# 3_PWR.net
KiCad netlist of a schematic drawn in Altium Designer
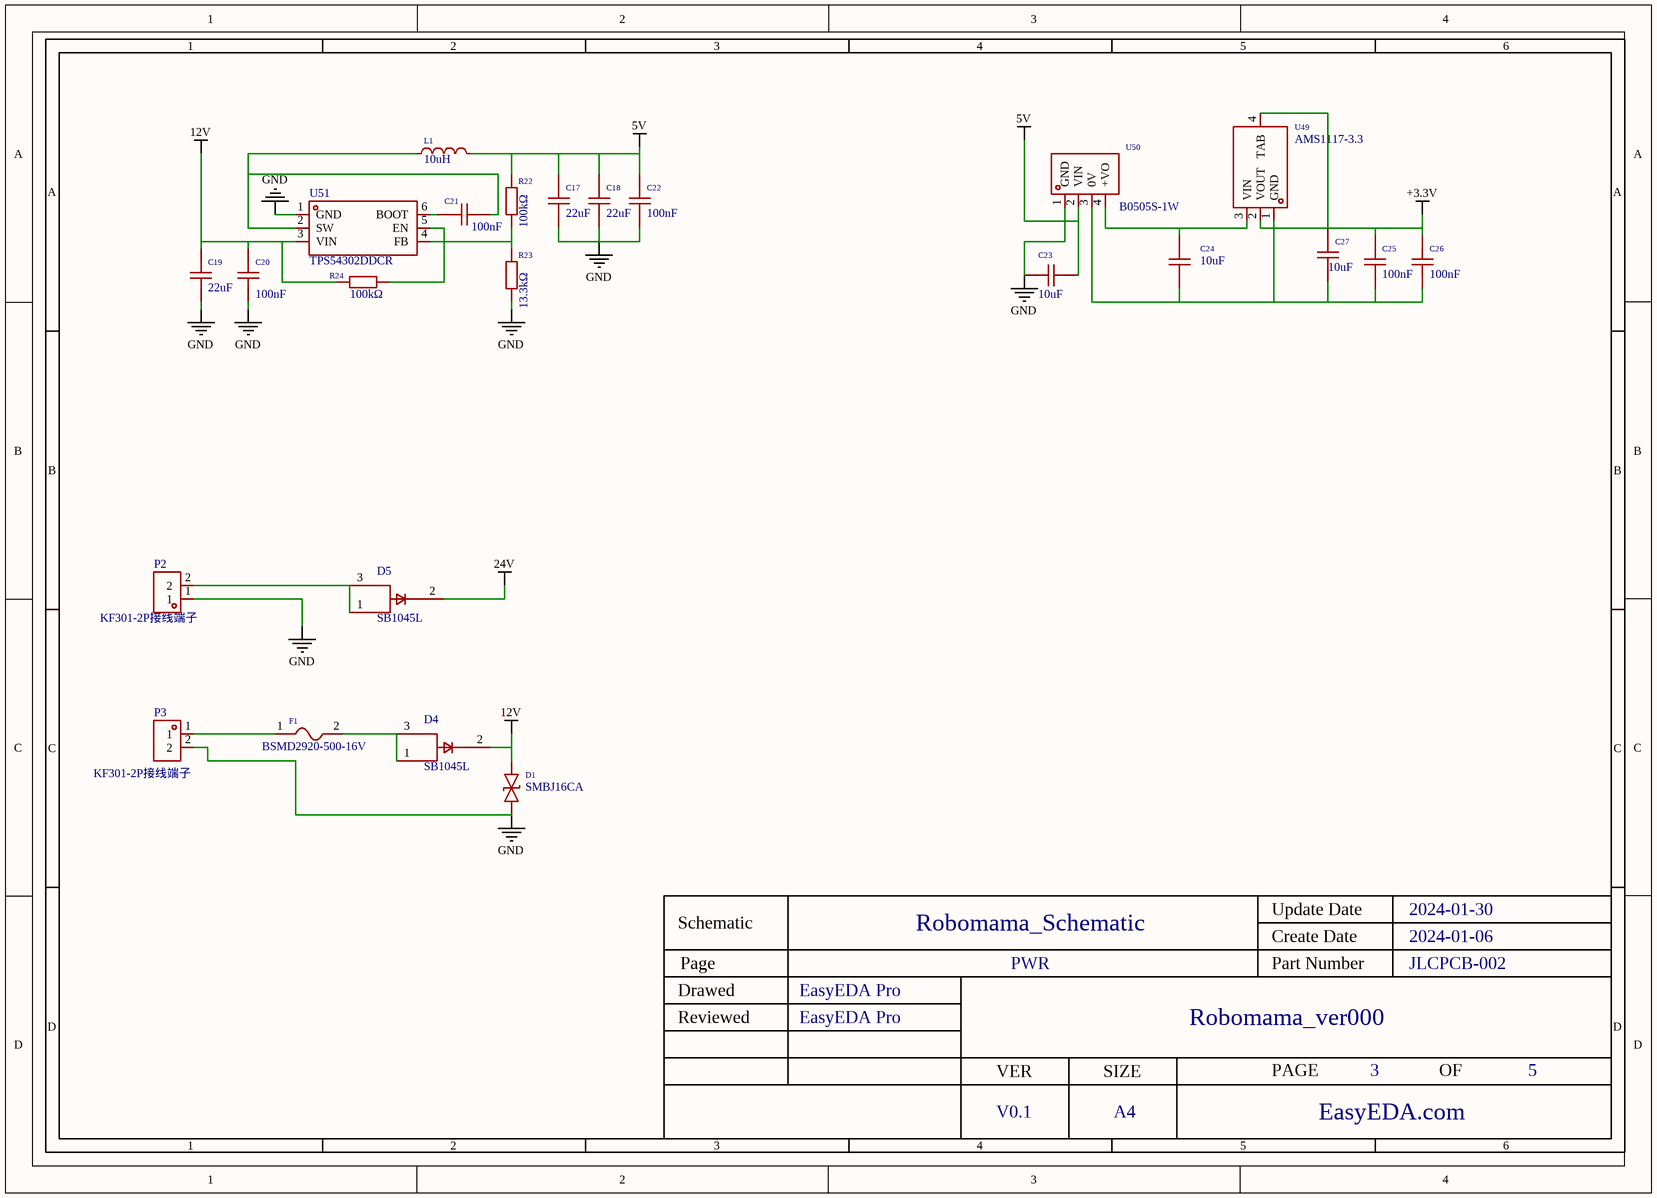
[diagram p0: 3_PWR.schdoc]

(export (version "E")
  (design (tool "Eeschema 10.0.6"))
  (components
    (comp (ref "C17")
      (value "22uF")
      (footprint "C0805")
      (fields
        (field (name "MANUFACTURER") "SAMSUNG(三星)")
        (field (name "MANUFACTURER PART") "CL21A226MAQNNNE")
        (field (name "TOLERANCE") "±20%")
      )
      (libsource (lib "altium-import") (part "root_1_CL21A226MAQNNNE_C45783_"))
    )
    (comp (ref "C18")
      (value "22uF")
      (footprint "C0805")
      (fields
        (field (name "MANUFACTURER") "SAMSUNG(三星)")
        (field (name "MANUFACTURER PART") "CL21A226MAQNNNE")
        (field (name "TOLERANCE") "±20%")
      )
      (libsource (lib "altium-import") (part "root_3_CL21A226MAQNNNE_C45783_"))
    )
    (comp (ref "C19")
      (value "22uF")
      (footprint "C0805")
      (fields
        (field (name "MANUFACTURER") "SAMSUNG(三星)")
        (field (name "MANUFACTURER PART") "CL21A226MAQNNNE")
        (field (name "TOLERANCE") "±20%")
      )
      (libsource (lib "altium-import") (part "root_1_CL21A226MAQNNNE_C45783_"))
    )
    (comp (ref "C20")
      (value "100nF")
      (footprint "C0603")
      (fields
        (field (name "MANUFACTURER") "YAGEO(国巨)")
        (field (name "MANUFACTURER PART") "CC0603KRX7R9BB104")
        (field (name "TOLERANCE") "±10%")
      )
      (libsource (lib "altium-import") (part "root_1_CC0603KRX7R9BB104_"))
    )
    (comp (ref "C21")
      (value "100nF")
      (footprint "C0603")
      (fields
        (field (name "MANUFACTURER") "YAGEO(国巨)")
        (field (name "MANUFACTURER PART") "CC0603KRX7R9BB104")
        (field (name "TOLERANCE") "±10%")
      )
      (libsource (lib "altium-import") (part "root_2_CC0603KRX7R9BB104_"))
    )
    (comp (ref "C22")
      (value "100nF")
      (footprint "C0603")
      (fields
        (field (name "MANUFACTURER") "YAGEO(国巨)")
        (field (name "MANUFACTURER PART") "CC0603KRX7R9BB104")
        (field (name "TOLERANCE") "±10%")
      )
      (libsource (lib "altium-import") (part "root_3_CC0603KRX7R9BB104_"))
    )
    (comp (ref "C23")
      (value "10uF")
      (footprint "C0603")
      (fields
        (field (name "MANUFACTURER") "SAMSUNG(三星)")
        (field (name "MANUFACTURER PART") "CL10A106KP8NNNC")
        (field (name "TOLERANCE") "±10%")
      )
      (libsource (lib "altium-import") (part "root_2_CL10A106KP8NNNC_"))
    )
    (comp (ref "C24")
      (value "10uF")
      (footprint "C0603")
      (fields
        (field (name "MANUFACTURER") "SAMSUNG(三星)")
        (field (name "MANUFACTURER PART") "CL10A106KP8NNNC")
        (field (name "TOLERANCE") "±10%")
      )
      (libsource (lib "altium-import") (part "root_1_CL10A106KP8NNNC_"))
    )
    (comp (ref "C25")
      (value "100nF")
      (footprint "C0603")
      (fields
        (field (name "MANUFACTURER") "YAGEO(国巨)")
        (field (name "MANUFACTURER PART") "CC0603KRX7R9BB104")
        (field (name "TOLERANCE") "±10%")
      )
      (libsource (lib "altium-import") (part "root_3_CC0603KRX7R9BB104_"))
    )
    (comp (ref "C26")
      (value "100nF")
      (footprint "C0603")
      (fields
        (field (name "MANUFACTURER") "YAGEO(国巨)")
        (field (name "MANUFACTURER PART") "CC0603KRX7R9BB104")
        (field (name "TOLERANCE") "±10%")
      )
      (libsource (lib "altium-import") (part "root_3_CC0603KRX7R9BB104_"))
    )
    (comp (ref "C27")
      (value "10uF")
      (footprint "C0603")
      (fields
        (field (name "MANUFACTURER") "SAMSUNG(三星)")
        (field (name "MANUFACTURER PART") "CL10A106KP8NNNC")
        (field (name "TOLERANCE") "±10%")
      )
      (libsource (lib "altium-import") (part "root_1_CL10A106KP8NNNC_"))
    )
    (comp (ref "D1")
      (value "SMBJ16CA")
      (footprint "SMB_L4.3-W3.6-LS5.4-BI")
      (fields (field (name "MANUFACTURER") "Brightking(君耀电子)"))
      (libsource (lib "altium-import") (part "root_1_SMBJ16CA_C194302_"))
    )
    (comp (ref "D4")
      (value "SB1045L")
      (footprint "TO-277_3P-L5.4-W4.0-LS6.5-TR")
      (description "Reverse Voltage (Vr):45V Average Rectified Current (Io):10A Forward Voltage (Vf@If):530mV@10A")
      (fields (field (name "MANUFACTURER") "MDD"))
      (libsource (lib "altium-import") (part "root_2_SB1045L_C113945_"))
    )
    (comp (ref "D5")
      (value "SB1045L")
      (footprint "TO-277_3P-L5.4-W4.0-LS6.5-TR")
      (description "Reverse Voltage (Vr):45V Average Rectified Current (Io):10A Forward Voltage (Vf@If):530mV@10A")
      (fields (field (name "MANUFACTURER") "MDD"))
      (libsource (lib "altium-import") (part "root_2_SB1045L_C113945_"))
    )
    (comp (ref "F1")
      (value "BSMD2920-500-16V")
      (footprint "F2920")
      (fields (field (name "MANUFACTURER") "BHFUSE(佰宏)"))
      (libsource (lib "altium-import") (part "root_0_BSMD2920-500-16V_"))
    )
    (comp (ref "L1")
      (value "10uH")
      (footprint "IND-SMD_L7.3-W6.8")
      (fields
        (field (name "MANUFACTURER") "cjiang(长江微电)")
        (field (name "MANUFACTURER PART") "FXL0630-100-M")
        (field (name "TOLERANCE") "±20%")
      )
      (libsource (lib "altium-import") (part "root_0_FXL0630-100-M_"))
    )
    (comp (ref "P2")
      (value "KF301-2P接线端子")
      (footprint "CONN-TH_XY301V-A-5.0-2P")
      (libsource (lib "altium-import") (part "root_2_KF301-2P接线端子_"))
    )
    (comp (ref "P3")
      (value "KF301-2P接线端子")
      (footprint "CONN-TH_XY301V-A-5.0-2P")
      (libsource (lib "altium-import") (part "root_0_mirrored_KF301-2P接线端子_"))
    )
    (comp (ref "R22")
      (value "100kΩ")
      (footprint "R0603")
      (fields
        (field (name "MANUFACTURER") "UNI-ROYAL(厚声)")
        (field (name "MANUFACTURER PART") "0603WAF1003T5E")
        (field (name "TOLERANCE") "±1%")
      )
      (libsource (lib "altium-import") (part "root_1_0603WAF1003T5E_"))
    )
    (comp (ref "R23")
      (value "13.3kΩ")
      (footprint "R0603")
      (fields
        (field (name "MANUFACTURER") "UNI-ROYAL(厚声)")
        (field (name "MANUFACTURER PART") "0603WAF1332T5E")
        (field (name "TOLERANCE") "±1%")
      )
      (libsource (lib "altium-import") (part "root_1_0603WAF1332T5E_"))
    )
    (comp (ref "R24")
      (value "100kΩ")
      (footprint "R0603")
      (fields
        (field (name "MANUFACTURER") "UNI-ROYAL(厚声)")
        (field (name "MANUFACTURER PART") "0603WAF1003T5E")
        (field (name "TOLERANCE") "±1%")
      )
      (libsource (lib "altium-import") (part "root_2_0603WAF1003T5E_"))
    )
    (comp (ref "U49")
      (value "AMS1117-3.3")
      (footprint "SOT-223-3_L6.5-W3.4-P2.30-LS7.0-BR")
      (fields (field (name "MANUFACTURER") "PUOLOP(迪浦)"))
      (libsource (lib "altium-import") (part "root_1_mirrored_AMS1117-3.3_C351784_"))
    )
    (comp (ref "U50")
      (value "B0505S-1W")
      (footprint "PWRM-TH_B0505S-1W")
      (fields (field (name "MANUFACTURER") "DEXU(德旭电子)"))
      (libsource (lib "altium-import") (part "root_0_B0505S-1W_C2912568_"))
    )
    (comp (ref "U51")
      (value "TPS54302DDCR")
      (footprint "SOT-23-6_L2.9-W1.6-P0.95-LS2.8-BL")
      (fields (field (name "MANUFACTURER") "TI(德州仪器)"))
      (libsource (lib "altium-import") (part "root_0_TPS54302DDCR_C311983_"))
    )
  )
  (nets
    (net (code "1") (name "+3.3V") (class "Default")
      (node (ref "C25") (pin "1") (pinfunction "1_1") (pintype "passive"))
      (node (ref "C26") (pin "1") (pinfunction "1_1") (pintype "passive"))
      (node (ref "C27") (pin "2") (pinfunction "2_2") (pintype "passive"))
      (node (ref "U49") (pin "2") (pinfunction "VOUT_2") (pintype "passive"))
      (node (ref "U49") (pin "4") (pinfunction "TAB_4") (pintype "passive"))
    )
    (net (code "2") (name "5V") (class "Default")
      (node (ref "C17") (pin "2") (pinfunction "2_2") (pintype "passive"))
      (node (ref "C18") (pin "1") (pinfunction "1_1") (pintype "passive"))
      (node (ref "C22") (pin "1") (pinfunction "1_1") (pintype "passive"))
      (node (ref "C23") (pin "1") (pinfunction "1_1") (pintype "passive"))
      (node (ref "L1") (pin "2") (pinfunction "2_2") (pintype "passive"))
      (node (ref "R22") (pin "2") (pinfunction "2_2") (pintype "passive"))
      (node (ref "U50") (pin "2") (pinfunction "VIN_2") (pintype "passive"))
    )
    (net (code "3") (name "12V") (class "Default")
      (node (ref "C19") (pin "2") (pinfunction "2_2") (pintype "passive"))
      (node (ref "C20") (pin "2") (pinfunction "2_2") (pintype "passive"))
      (node (ref "D1") (pin "2") (pinfunction "2_2") (pintype "passive"))
      (node (ref "D4") (pin "2") (pinfunction "K_2") (pintype "passive"))
      (node (ref "R24") (pin "2") (pinfunction "2_2") (pintype "passive"))
      (node (ref "U51") (pin "3") (pinfunction "VIN_3") (pintype "passive"))
    )
    (net (code "4") (name "24V") (class "Default")
      (node (ref "D5") (pin "2") (pinfunction "K_2") (pintype "passive"))
    )
    (net (code "5") (name "GND") (class "Default")
      (node (ref "C17") (pin "1") (pinfunction "1_1") (pintype "passive"))
      (node (ref "C18") (pin "2") (pinfunction "2_2") (pintype "passive"))
      (node (ref "C19") (pin "1") (pinfunction "1_1") (pintype "passive"))
      (node (ref "C20") (pin "1") (pinfunction "1_1") (pintype "passive"))
      (node (ref "C22") (pin "2") (pinfunction "2_2") (pintype "passive"))
      (node (ref "C23") (pin "2") (pinfunction "2_2") (pintype "passive"))
      (node (ref "D1") (pin "1") (pinfunction "1_1") (pintype "passive"))
      (node (ref "P2") (pin "1") (pinfunction "1_1") (pintype "passive"))
      (node (ref "P3") (pin "2") (pinfunction "2_2") (pintype "passive"))
      (node (ref "R23") (pin "1") (pinfunction "1_1") (pintype "passive"))
      (node (ref "U50") (pin "1") (pinfunction "GND_1") (pintype "passive"))
      (node (ref "U51") (pin "1") (pinfunction "GND_1") (pintype "passive"))
    )
    (net (code "6") (name "Net-(D4-A-Pad1)") (class "Default")
      (node (ref "D4") (pin "1") (pinfunction "A_1") (pintype "passive"))
      (node (ref "D4") (pin "3") (pinfunction "A_3") (pintype "passive"))
      (node (ref "F1") (pin "2") (pinfunction "2_2") (pintype "passive"))
    )
    (net (code "7") (name "Net-(D5-A-Pad1)") (class "Default")
      (node (ref "D5") (pin "1") (pinfunction "A_1") (pintype "passive"))
      (node (ref "D5") (pin "3") (pinfunction "A_3") (pintype "passive"))
      (node (ref "P2") (pin "2") (pinfunction "2_2") (pintype "passive"))
    )
    (net (code "8") (name "Net-(F1-Pad1)") (class "Default")
      (node (ref "F1") (pin "1") (pinfunction "1_1") (pintype "passive"))
      (node (ref "P3") (pin "1") (pinfunction "1_1") (pintype "passive"))
    )
    (net (code "9") (name "Net-(U49-GND)") (class "Default")
      (node (ref "C24") (pin "1") (pinfunction "1_1") (pintype "passive"))
      (node (ref "C25") (pin "2") (pinfunction "2_2") (pintype "passive"))
      (node (ref "C26") (pin "2") (pinfunction "2_2") (pintype "passive"))
      (node (ref "C27") (pin "1") (pinfunction "1_1") (pintype "passive"))
      (node (ref "U49") (pin "1") (pinfunction "GND_1") (pintype "passive"))
      (node (ref "U50") (pin "3") (pinfunction "0V_3") (pintype "passive"))
    )
    (net (code "10") (name "Net-(U49-VIN)") (class "Default")
      (node (ref "C24") (pin "2") (pinfunction "2_2") (pintype "passive"))
      (node (ref "U49") (pin "3") (pinfunction "VIN_3") (pintype "passive"))
      (node (ref "U50") (pin "4") (pinfunction "+VO_4") (pintype "passive"))
    )
    (net (code "11") (name "Net-(U51-BOOT)") (class "Default")
      (node (ref "C21") (pin "2") (pinfunction "2_2") (pintype "passive"))
      (node (ref "U51") (pin "6") (pinfunction "BOOT_6") (pintype "passive"))
    )
    (net (code "12") (name "Net-(U51-EN)") (class "Default")
      (node (ref "R24") (pin "1") (pinfunction "1_1") (pintype "passive"))
      (node (ref "U51") (pin "5") (pinfunction "EN_5") (pintype "passive"))
    )
    (net (code "13") (name "Net-(U51-FB)") (class "Default")
      (node (ref "R22") (pin "1") (pinfunction "1_1") (pintype "passive"))
      (node (ref "R23") (pin "2") (pinfunction "2_2") (pintype "passive"))
      (node (ref "U51") (pin "4") (pinfunction "FB_4") (pintype "passive"))
    )
    (net (code "14") (name "Net-(U51-SW)") (class "Default")
      (node (ref "C21") (pin "1") (pinfunction "1_1") (pintype "passive"))
      (node (ref "L1") (pin "1") (pinfunction "1_1") (pintype "passive"))
      (node (ref "U51") (pin "2") (pinfunction "SW_2") (pintype "passive"))
    )
  )
)
